# BEESP12.net
KiCad netlist of a schematic drawn in EAGLE
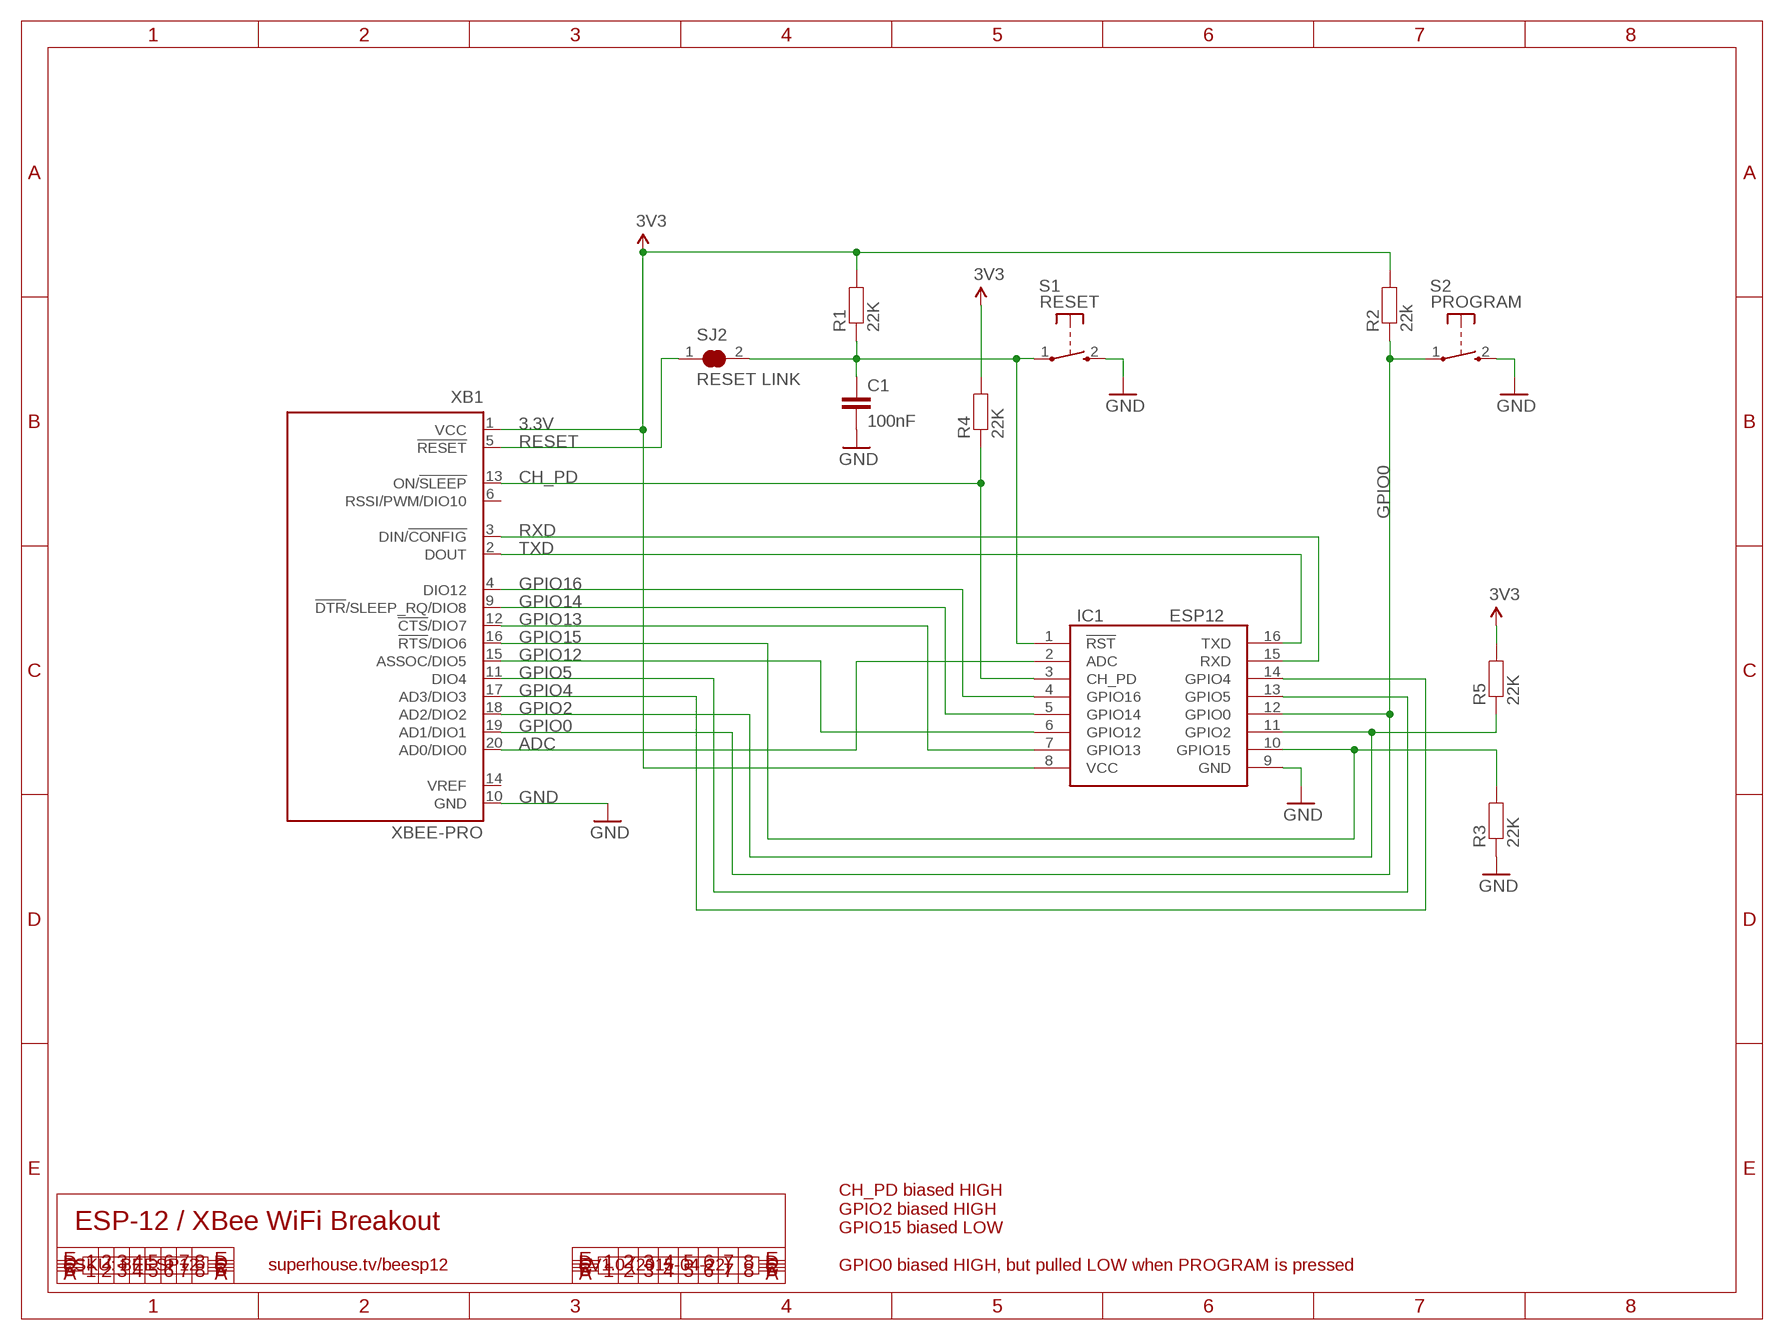
[diagram p0: schematic, sheet 1]

(export (version "E")
  (design (tool "Eeschema 10.0.6"))
  (components
    (comp (ref "C1")
      (value "100nF")
      (footprint "eagle-import:0603")
      (libsource (lib "eagle-import") (part "CAP0603"))
    )
    (comp (ref "IC1")
      (value "ESP12")
      (footprint "eagle-import:ESP12")
      (libsource (lib "eagle-import") (part "ESP12"))
    )
    (comp (ref "R1")
      (value "22K")
      (footprint "eagle-import:0603")
      (libsource (lib "eagle-import") (part "RESISTOR0603"))
    )
    (comp (ref "R2")
      (value "22k")
      (footprint "eagle-import:0603")
      (libsource (lib "eagle-import") (part "RESISTOR0603"))
    )
    (comp (ref "R3")
      (value "22K")
      (footprint "eagle-import:0603")
      (libsource (lib "eagle-import") (part "RESISTOR0603"))
    )
    (comp (ref "R4")
      (value "22K")
      (footprint "eagle-import:0603")
      (libsource (lib "eagle-import") (part "RESISTOR0603"))
    )
    (comp (ref "R5")
      (value "22K")
      (footprint "eagle-import:0603")
      (libsource (lib "eagle-import") (part "RESISTOR0603"))
    )
    (comp (ref "S1")
      (value "RESET")
      (footprint "eagle-import:TACTILE_SWITCH_SMD_2PIN_TINY")
      (libsource (lib "eagle-import") (part "TAC_SWITCH_2PIN"))
    )
    (comp (ref "S2")
      (value "PROGRAM")
      (footprint "eagle-import:TACTILE_SWITCH_SMD_2PIN_TINY")
      (libsource (lib "eagle-import") (part "TAC_SWITCH_2PIN"))
    )
    (comp (ref "SJ2")
      (value "RESET LINK")
      (footprint "eagle-import:SJC")
      (libsource (lib "eagle-import") (part "SJCN"))
    )
    (comp (ref "XB1")
      (value "XBEE-PRO")
      (footprint "eagle-import:XBEE-PRO")
      (fields (field (name "MPN") "XBP24-AWI-001"))
      (libsource (lib "eagle-import") (part "XBEE-PRO"))
    )
  )
  (nets
    (net (code "1") (name "/ADC") (class "Default")
      (node (ref "IC1") (pin "2") (pinfunction "ADC_2") (pintype "input"))
      (node (ref "XB1") (pin "20") (pinfunction "AD0/DIO0_20") (pintype "bidirectional"))
    )
    (net (code "2") (name "/CH_PD") (class "Default")
      (node (ref "IC1") (pin "3") (pinfunction "CH_PD_3") (pintype "input"))
      (node (ref "R4") (pin "1") (pinfunction "1_1") (pintype "passive"))
      (node (ref "XB1") (pin "13") (pinfunction "ON/~{SLEEP}_13") (pintype "output"))
    )
    (net (code "3") (name "/GPIO0") (class "Default")
      (node (ref "IC1") (pin "12") (pinfunction "GPIO0_12") (pintype "bidirectional"))
      (node (ref "R2") (pin "1") (pinfunction "1_1") (pintype "passive"))
      (node (ref "S2") (pin "1") (pinfunction "P_1") (pintype "passive"))
      (node (ref "XB1") (pin "19") (pinfunction "AD1/DIO1_19") (pintype "bidirectional"))
    )
    (net (code "4") (name "/GPIO2") (class "Default")
      (node (ref "IC1") (pin "11") (pinfunction "GPIO2_11") (pintype "bidirectional"))
      (node (ref "R5") (pin "1") (pinfunction "1_1") (pintype "passive"))
      (node (ref "XB1") (pin "18") (pinfunction "AD2/DIO2_18") (pintype "bidirectional"))
    )
    (net (code "5") (name "/GPIO4") (class "Default")
      (node (ref "IC1") (pin "14") (pinfunction "GPIO4_14") (pintype "bidirectional"))
      (node (ref "XB1") (pin "17") (pinfunction "AD3/DIO3_17") (pintype "bidirectional"))
    )
    (net (code "6") (name "/GPIO5") (class "Default")
      (node (ref "IC1") (pin "13") (pinfunction "GPIO5_13") (pintype "bidirectional"))
      (node (ref "XB1") (pin "11") (pinfunction "DIO4_11") (pintype "bidirectional"))
    )
    (net (code "7") (name "/GPIO12") (class "Default")
      (node (ref "IC1") (pin "6") (pinfunction "GPIO12_6") (pintype "bidirectional"))
      (node (ref "XB1") (pin "15") (pinfunction "ASSOC/DIO5_15") (pintype "bidirectional"))
    )
    (net (code "8") (name "/GPIO13") (class "Default")
      (node (ref "IC1") (pin "7") (pinfunction "GPIO13_7") (pintype "bidirectional"))
      (node (ref "XB1") (pin "12") (pinfunction "~{CTS}/DIO7_12") (pintype "bidirectional"))
    )
    (net (code "9") (name "/GPIO14") (class "Default")
      (node (ref "IC1") (pin "5") (pinfunction "GPIO14_5") (pintype "bidirectional"))
      (node (ref "XB1") (pin "9") (pinfunction "~{DTR}/SLEEP_RQ/DIO8_9") (pintype "bidirectional"))
    )
    (net (code "10") (name "/GPIO15") (class "Default")
      (node (ref "IC1") (pin "10") (pinfunction "GPIO15_10") (pintype "bidirectional"))
      (node (ref "R3") (pin "2") (pinfunction "2_2") (pintype "passive"))
      (node (ref "XB1") (pin "16") (pinfunction "~{RTS}/DIO6_16") (pintype "bidirectional"))
    )
    (net (code "11") (name "/GPIO16") (class "Default")
      (node (ref "IC1") (pin "4") (pinfunction "GPIO16_4") (pintype "bidirectional"))
      (node (ref "XB1") (pin "4") (pinfunction "DIO12_4") (pintype "bidirectional"))
    )
    (net (code "12") (name "/RESET") (class "Default")
      (node (ref "SJ2") (pin "1") (pinfunction "1_1") (pintype "passive"))
      (node (ref "XB1") (pin "5") (pinfunction "~{RESET}_5") (pintype "input"))
    )
    (net (code "13") (name "/RXD") (class "Default")
      (node (ref "IC1") (pin "15") (pinfunction "RXD_15") (pintype "input"))
      (node (ref "XB1") (pin "3") (pinfunction "DIN/~{CONFIG}_3") (pintype "input"))
    )
    (net (code "14") (name "/TXD") (class "Default")
      (node (ref "IC1") (pin "16") (pinfunction "TXD_16") (pintype "output"))
      (node (ref "XB1") (pin "2") (pinfunction "DOUT_2") (pintype "output"))
    )
    (net (code "15") (name "3V3") (class "Default")
      (node (ref "IC1") (pin "8") (pinfunction "VCC_8") (pintype "power_in"))
      (node (ref "R1") (pin "2") (pinfunction "2_2") (pintype "passive"))
      (node (ref "R2") (pin "2") (pinfunction "2_2") (pintype "passive"))
      (node (ref "R4") (pin "2") (pinfunction "2_2") (pintype "passive"))
      (node (ref "R5") (pin "2") (pinfunction "2_2") (pintype "passive"))
      (node (ref "XB1") (pin "1") (pinfunction "VCC_1") (pintype "power_in"))
    )
    (net (code "16") (name "GND") (class "Default")
      (node (ref "C1") (pin "2") (pinfunction "2_2") (pintype "passive"))
      (node (ref "IC1") (pin "9") (pinfunction "GND_9") (pintype "power_in"))
      (node (ref "R3") (pin "1") (pinfunction "1_1") (pintype "passive"))
      (node (ref "S1") (pin "2") (pinfunction "S_2") (pintype "passive"))
      (node (ref "S2") (pin "2") (pinfunction "S_2") (pintype "passive"))
      (node (ref "XB1") (pin "10") (pinfunction "GND_10") (pintype "power_in"))
    )
    (net (code "17") (name "Net-(IC1-~{RST})") (class "Default")
      (node (ref "C1") (pin "1") (pinfunction "1_1") (pintype "passive"))
      (node (ref "IC1") (pin "1") (pinfunction "~{RST}_1") (pintype "bidirectional"))
      (node (ref "R1") (pin "1") (pinfunction "1_1") (pintype "passive"))
      (node (ref "S1") (pin "1") (pinfunction "P_1") (pintype "passive"))
      (node (ref "SJ2") (pin "2") (pinfunction "2_2") (pintype "passive"))
    )
    (net (code "18") (name "unconnected-(XB1-RSSI{slash}PWM{slash}DIO10-Pad6)") (class "Default")
      (node (ref "XB1") (pin "6") (pinfunction "RSSI/PWM/DIO10_6") (pintype "output"))
    )
    (net (code "19") (name "unconnected-(XB1-VREF-Pad14)") (class "Default")
      (node (ref "XB1") (pin "14") (pinfunction "VREF_14") (pintype "input"))
    )
  )
)
